# untitled.net
KiCad netlist of a schematic drawn in EAGLE
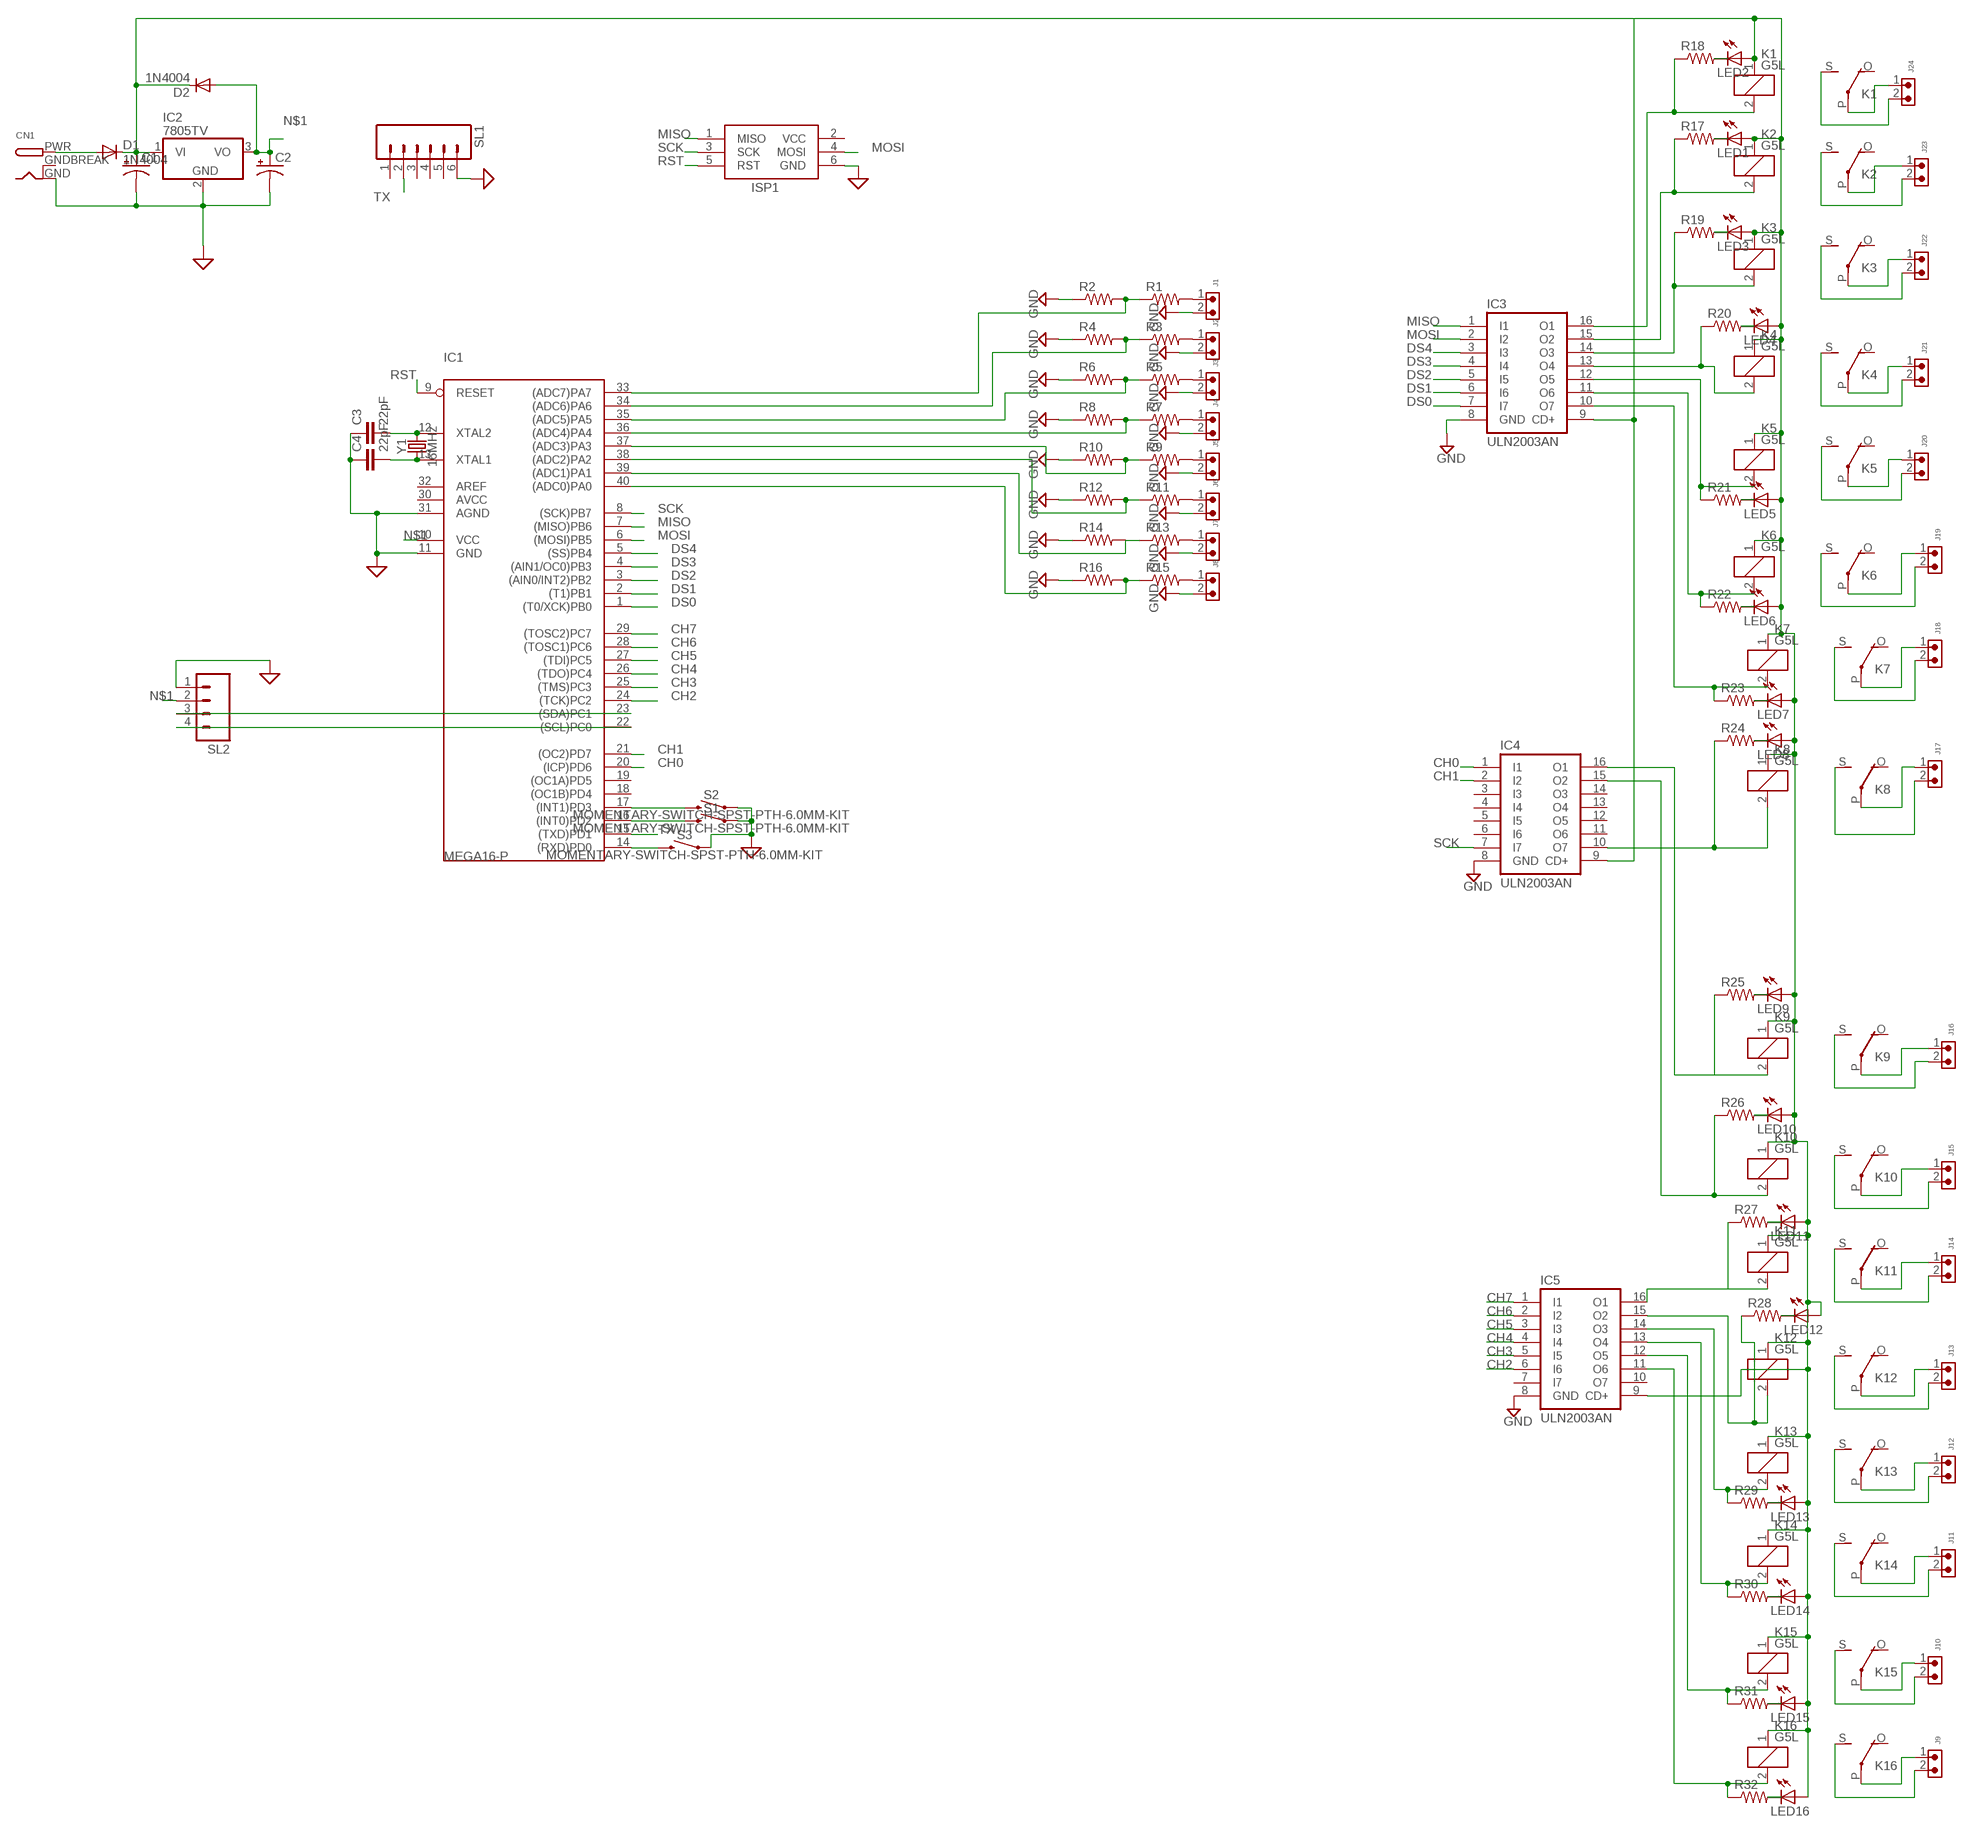
[diagram p0: schematic, sheet 1]

(export (version "E")
  (design (tool "Eeschema 10.0.6"))
  (components
    (comp (ref "C1")
      (value "CAPACITOR-PE5-10.5")
      (footprint "eagle-import:E5-10,5")
      (libsource (lib "eagle-import") (part "CAPACITOR-PE5-10.5"))
    )
    (comp (ref "C2")
      (value "CAPACITOR-PE5-6")
      (footprint "eagle-import:E5-6")
      (libsource (lib "eagle-import") (part "CAPACITOR-PE5-6"))
    )
    (comp (ref "C3")
      (value "22pF")
      (footprint "eagle-import:CAP-PTH-2.54")
      (libsource (lib "eagle-import") (part "22PF-PTH-2.54MM-200V-5%"))
    )
    (comp (ref "C4")
      (value "22pF")
      (footprint "eagle-import:CAP-PTH-2.54")
      (libsource (lib "eagle-import") (part "22PF-PTH-2.54MM-200V-5%"))
    )
    (comp (ref "CN1")
      (value "DCBARRELPTH")
      (footprint "eagle-import:DCJACK_2MM_PTH")
      (libsource (lib "eagle-import") (part "DCBARRELPTH"))
    )
    (comp (ref "D1")
      (value "1N4004")
      (footprint "eagle-import:DO41-10")
      (libsource (lib "eagle-import") (part "1N4004"))
    )
    (comp (ref "D2")
      (value "1N4004")
      (footprint "eagle-import:DO41-10")
      (libsource (lib "eagle-import") (part "1N4004"))
    )
    (comp (ref "IC1")
      (value "MEGA16-P")
      (footprint "eagle-import:DIL40")
      (libsource (lib "eagle-import") (part "MEGA16-P"))
    )
    (comp (ref "IC2")
      (value "7805TV")
      (footprint "eagle-import:TO220V")
      (libsource (lib "eagle-import") (part "78TV05"))
    )
    (comp (ref "IC3")
      (value "ULN2003AN")
      (footprint "eagle-import:DIL16")
      (libsource (lib "eagle-import") (part "ULN2003AN"))
    )
    (comp (ref "IC4")
      (value "ULN2003AN")
      (footprint "eagle-import:DIL16")
      (libsource (lib "eagle-import") (part "ULN2003AN"))
    )
    (comp (ref "IC5")
      (value "ULN2003AN")
      (footprint "eagle-import:DIL16")
      (libsource (lib "eagle-import") (part "ULN2003AN"))
    )
    (comp (ref "ISP1")
      (value "AVRISP-6")
      (footprint "eagle-import:AVRISP")
      (libsource (lib "eagle-import") (part "AVRISP-6"))
    )
    (comp (ref "J1")
      (value "691305530002")
      (footprint "eagle-import:691305530002")
      (libsource (lib "eagle-import") (part "691305530002"))
    )
    (comp (ref "J2")
      (value "691305530002")
      (footprint "eagle-import:691305530002")
      (libsource (lib "eagle-import") (part "691305530002"))
    )
    (comp (ref "J3")
      (value "691305530002")
      (footprint "eagle-import:691305530002")
      (libsource (lib "eagle-import") (part "691305530002"))
    )
    (comp (ref "J4")
      (value "691305530002")
      (footprint "eagle-import:691305530002")
      (libsource (lib "eagle-import") (part "691305530002"))
    )
    (comp (ref "J5")
      (value "691305530002")
      (footprint "eagle-import:691305530002")
      (libsource (lib "eagle-import") (part "691305530002"))
    )
    (comp (ref "J6")
      (value "691305530002")
      (footprint "eagle-import:691305530002")
      (libsource (lib "eagle-import") (part "691305530002"))
    )
    (comp (ref "J7")
      (value "691305530002")
      (footprint "eagle-import:691305530002")
      (libsource (lib "eagle-import") (part "691305530002"))
    )
    (comp (ref "J8")
      (value "691305530002")
      (footprint "eagle-import:691305530002")
      (libsource (lib "eagle-import") (part "691305530002"))
    )
    (comp (ref "J9")
      (value "691305530002")
      (footprint "eagle-import:691305530002")
      (libsource (lib "eagle-import") (part "691305530002"))
    )
    (comp (ref "J10")
      (value "691305530002")
      (footprint "eagle-import:691305530002")
      (libsource (lib "eagle-import") (part "691305530002"))
    )
    (comp (ref "J11")
      (value "691305530002")
      (footprint "eagle-import:691305530002")
      (libsource (lib "eagle-import") (part "691305530002"))
    )
    (comp (ref "J12")
      (value "691305530002")
      (footprint "eagle-import:691305530002")
      (libsource (lib "eagle-import") (part "691305530002"))
    )
    (comp (ref "J13")
      (value "691305530002")
      (footprint "eagle-import:691305530002")
      (libsource (lib "eagle-import") (part "691305530002"))
    )
    (comp (ref "J14")
      (value "691305530002")
      (footprint "eagle-import:691305530002")
      (libsource (lib "eagle-import") (part "691305530002"))
    )
    (comp (ref "J15")
      (value "691305530002")
      (footprint "eagle-import:691305530002")
      (libsource (lib "eagle-import") (part "691305530002"))
    )
    (comp (ref "J16")
      (value "691305530002")
      (footprint "eagle-import:691305530002")
      (libsource (lib "eagle-import") (part "691305530002"))
    )
    (comp (ref "J17")
      (value "691305530002")
      (footprint "eagle-import:691305530002")
      (libsource (lib "eagle-import") (part "691305530002"))
    )
    (comp (ref "J18")
      (value "691305530002")
      (footprint "eagle-import:691305530002")
      (libsource (lib "eagle-import") (part "691305530002"))
    )
    (comp (ref "J19")
      (value "691305530002")
      (footprint "eagle-import:691305530002")
      (libsource (lib "eagle-import") (part "691305530002"))
    )
    (comp (ref "J20")
      (value "691305530002")
      (footprint "eagle-import:691305530002")
      (libsource (lib "eagle-import") (part "691305530002"))
    )
    (comp (ref "J21")
      (value "691305530002")
      (footprint "eagle-import:691305530002")
      (libsource (lib "eagle-import") (part "691305530002"))
    )
    (comp (ref "J22")
      (value "691305530002")
      (footprint "eagle-import:691305530002")
      (libsource (lib "eagle-import") (part "691305530002"))
    )
    (comp (ref "J23")
      (value "691305530002")
      (footprint "eagle-import:691305530002")
      (libsource (lib "eagle-import") (part "691305530002"))
    )
    (comp (ref "J24")
      (value "691305530002")
      (footprint "eagle-import:691305530002")
      (libsource (lib "eagle-import") (part "691305530002"))
    )
    (comp (ref "K1")
      (value "G5L")
      (footprint "eagle-import:G5LE")
      (libsource (lib "eagle-import") (part "G5L"))
    )
    (comp (ref "K2")
      (value "G5L")
      (footprint "eagle-import:G5LE")
      (libsource (lib "eagle-import") (part "G5L"))
    )
    (comp (ref "K3")
      (value "G5L")
      (footprint "eagle-import:G5LE")
      (libsource (lib "eagle-import") (part "G5L"))
    )
    (comp (ref "K4")
      (value "G5L")
      (footprint "eagle-import:G5LE")
      (libsource (lib "eagle-import") (part "G5L"))
    )
    (comp (ref "K5")
      (value "G5L")
      (footprint "eagle-import:G5LE")
      (libsource (lib "eagle-import") (part "G5L"))
    )
    (comp (ref "K6")
      (value "G5L")
      (footprint "eagle-import:G5LE")
      (libsource (lib "eagle-import") (part "G5L"))
    )
    (comp (ref "K7")
      (value "G5L")
      (footprint "eagle-import:G5LE")
      (libsource (lib "eagle-import") (part "G5L"))
    )
    (comp (ref "K8")
      (value "G5L")
      (footprint "eagle-import:G5LE")
      (libsource (lib "eagle-import") (part "G5L"))
    )
    (comp (ref "K9")
      (value "G5L")
      (footprint "eagle-import:G5LE")
      (libsource (lib "eagle-import") (part "G5L"))
    )
    (comp (ref "K10")
      (value "G5L")
      (footprint "eagle-import:G5LE")
      (libsource (lib "eagle-import") (part "G5L"))
    )
    (comp (ref "K11")
      (value "G5L")
      (footprint "eagle-import:G5LE")
      (libsource (lib "eagle-import") (part "G5L"))
    )
    (comp (ref "K12")
      (value "G5L")
      (footprint "eagle-import:G5LE")
      (libsource (lib "eagle-import") (part "G5L"))
    )
    (comp (ref "K13")
      (value "G5L")
      (footprint "eagle-import:G5LE")
      (libsource (lib "eagle-import") (part "G5L"))
    )
    (comp (ref "K14")
      (value "G5L")
      (footprint "eagle-import:G5LE")
      (libsource (lib "eagle-import") (part "G5L"))
    )
    (comp (ref "K15")
      (value "G5L")
      (footprint "eagle-import:G5LE")
      (libsource (lib "eagle-import") (part "G5L"))
    )
    (comp (ref "K16")
      (value "G5L")
      (footprint "eagle-import:G5LE")
      (libsource (lib "eagle-import") (part "G5L"))
    )
    (comp (ref "LED1")
      (value "LED5MM")
      (footprint "eagle-import:LED5MM")
      (libsource (lib "eagle-import") (part "LED5MM"))
    )
    (comp (ref "LED2")
      (value "LED5MM")
      (footprint "eagle-import:LED5MM")
      (libsource (lib "eagle-import") (part "LED5MM"))
    )
    (comp (ref "LED3")
      (value "LED5MM")
      (footprint "eagle-import:LED5MM")
      (libsource (lib "eagle-import") (part "LED5MM"))
    )
    (comp (ref "LED4")
      (value "LED5MM")
      (footprint "eagle-import:LED5MM")
      (libsource (lib "eagle-import") (part "LED5MM"))
    )
    (comp (ref "LED5")
      (value "LED5MM")
      (footprint "eagle-import:LED5MM")
      (libsource (lib "eagle-import") (part "LED5MM"))
    )
    (comp (ref "LED6")
      (value "LED5MM")
      (footprint "eagle-import:LED5MM")
      (libsource (lib "eagle-import") (part "LED5MM"))
    )
    (comp (ref "LED7")
      (value "LED5MM")
      (footprint "eagle-import:LED5MM")
      (libsource (lib "eagle-import") (part "LED5MM"))
    )
    (comp (ref "LED8")
      (value "LED5MM")
      (footprint "eagle-import:LED5MM")
      (libsource (lib "eagle-import") (part "LED5MM"))
    )
    (comp (ref "LED9")
      (value "LED5MM")
      (footprint "eagle-import:LED5MM")
      (libsource (lib "eagle-import") (part "LED5MM"))
    )
    (comp (ref "LED10")
      (value "LED5MM")
      (footprint "eagle-import:LED5MM")
      (libsource (lib "eagle-import") (part "LED5MM"))
    )
    (comp (ref "LED11")
      (value "LED5MM")
      (footprint "eagle-import:LED5MM")
      (libsource (lib "eagle-import") (part "LED5MM"))
    )
    (comp (ref "LED12")
      (value "LED5MM")
      (footprint "eagle-import:LED5MM")
      (libsource (lib "eagle-import") (part "LED5MM"))
    )
    (comp (ref "LED13")
      (value "LED5MM")
      (footprint "eagle-import:LED5MM")
      (libsource (lib "eagle-import") (part "LED5MM"))
    )
    (comp (ref "LED14")
      (value "LED5MM")
      (footprint "eagle-import:LED5MM")
      (libsource (lib "eagle-import") (part "LED5MM"))
    )
    (comp (ref "LED15")
      (value "LED5MM")
      (footprint "eagle-import:LED5MM")
      (libsource (lib "eagle-import") (part "LED5MM"))
    )
    (comp (ref "LED16")
      (value "LED5MM")
      (footprint "eagle-import:LED5MM")
      (libsource (lib "eagle-import") (part "LED5MM"))
    )
    (comp (ref "R1")
      (value "R-US_0309/12")
      (footprint "eagle-import:0309_12")
      (libsource (lib "eagle-import") (part "R-US_0309/12"))
    )
    (comp (ref "R2")
      (value "R-US_0309/12")
      (footprint "eagle-import:0309_12")
      (libsource (lib "eagle-import") (part "R-US_0309/12"))
    )
    (comp (ref "R3")
      (value "R-US_0309/12")
      (footprint "eagle-import:0309_12")
      (libsource (lib "eagle-import") (part "R-US_0309/12"))
    )
    (comp (ref "R4")
      (value "R-US_0309/12")
      (footprint "eagle-import:0309_12")
      (libsource (lib "eagle-import") (part "R-US_0309/12"))
    )
    (comp (ref "R5")
      (value "R-US_0309/12")
      (footprint "eagle-import:0309_12")
      (libsource (lib "eagle-import") (part "R-US_0309/12"))
    )
    (comp (ref "R6")
      (value "R-US_0309/12")
      (footprint "eagle-import:0309_12")
      (libsource (lib "eagle-import") (part "R-US_0309/12"))
    )
    (comp (ref "R7")
      (value "R-US_0309/12")
      (footprint "eagle-import:0309_12")
      (libsource (lib "eagle-import") (part "R-US_0309/12"))
    )
    (comp (ref "R8")
      (value "R-US_0309/12")
      (footprint "eagle-import:0309_12")
      (libsource (lib "eagle-import") (part "R-US_0309/12"))
    )
    (comp (ref "R9")
      (value "R-US_0309/12")
      (footprint "eagle-import:0309_12")
      (libsource (lib "eagle-import") (part "R-US_0309/12"))
    )
    (comp (ref "R10")
      (value "R-US_0309/12")
      (footprint "eagle-import:0309_12")
      (libsource (lib "eagle-import") (part "R-US_0309/12"))
    )
    (comp (ref "R11")
      (value "R-US_0309/12")
      (footprint "eagle-import:0309_12")
      (libsource (lib "eagle-import") (part "R-US_0309/12"))
    )
    (comp (ref "R12")
      (value "R-US_0309/12")
      (footprint "eagle-import:0309_12")
      (libsource (lib "eagle-import") (part "R-US_0309/12"))
    )
    (comp (ref "R13")
      (value "R-US_0309/12")
      (footprint "eagle-import:0309_12")
      (libsource (lib "eagle-import") (part "R-US_0309/12"))
    )
    (comp (ref "R14")
      (value "R-US_0309/12")
      (footprint "eagle-import:0309_12")
      (libsource (lib "eagle-import") (part "R-US_0309/12"))
    )
    (comp (ref "R15")
      (value "R-US_0309/12")
      (footprint "eagle-import:0309_12")
      (libsource (lib "eagle-import") (part "R-US_0309/12"))
    )
    (comp (ref "R16")
      (value "R-US_0309/12")
      (footprint "eagle-import:0309_12")
      (libsource (lib "eagle-import") (part "R-US_0309/12"))
    )
    (comp (ref "R17")
      (value "R-US_0204/5")
      (footprint "eagle-import:0204_5")
      (libsource (lib "eagle-import") (part "adafruit_420_R-US_0204/5"))
    )
    (comp (ref "R18")
      (value "R-US_0204/5")
      (footprint "eagle-import:0204_5")
      (libsource (lib "eagle-import") (part "adafruit_420_R-US_0204/5"))
    )
    (comp (ref "R19")
      (value "R-US_0204/5")
      (footprint "eagle-import:0204_5")
      (libsource (lib "eagle-import") (part "adafruit_420_R-US_0204/5"))
    )
    (comp (ref "R20")
      (value "R-US_0204/5")
      (footprint "eagle-import:0204_5")
      (libsource (lib "eagle-import") (part "adafruit_420_R-US_0204/5"))
    )
    (comp (ref "R21")
      (value "R-US_0204/5")
      (footprint "eagle-import:0204_5")
      (libsource (lib "eagle-import") (part "adafruit_420_R-US_0204/5"))
    )
    (comp (ref "R22")
      (value "R-US_0207/10")
      (footprint "eagle-import:0207_10")
      (libsource (lib "eagle-import") (part "adafruit_420_R-US_0207/10"))
    )
    (comp (ref "R23")
      (value "R-US_0207/10")
      (footprint "eagle-import:0207_10")
      (libsource (lib "eagle-import") (part "adafruit_420_R-US_0207/10"))
    )
    (comp (ref "R24")
      (value "R-US_0204/5")
      (footprint "eagle-import:0204_5")
      (libsource (lib "eagle-import") (part "adafruit_420_R-US_0204/5"))
    )
    (comp (ref "R25")
      (value "R-US_0207/10")
      (footprint "eagle-import:0207_10")
      (libsource (lib "eagle-import") (part "adafruit_420_R-US_0207/10"))
    )
    (comp (ref "R26")
      (value "R-US_0207/10")
      (footprint "eagle-import:0207_10")
      (libsource (lib "eagle-import") (part "adafruit_420_R-US_0207/10"))
    )
    (comp (ref "R27")
      (value "R-US_0207/10")
      (footprint "eagle-import:0207_10")
      (libsource (lib "eagle-import") (part "adafruit_420_R-US_0207/10"))
    )
    (comp (ref "R28")
      (value "R-US_0207/10")
      (footprint "eagle-import:0207_10")
      (libsource (lib "eagle-import") (part "adafruit_420_R-US_0207/10"))
    )
    (comp (ref "R29")
      (value "R-US_0207/10")
      (footprint "eagle-import:0207_10")
      (libsource (lib "eagle-import") (part "adafruit_420_R-US_0207/10"))
    )
    (comp (ref "R30")
      (value "R-US_0207/10")
      (footprint "eagle-import:0207_10")
      (libsource (lib "eagle-import") (part "adafruit_420_R-US_0207/10"))
    )
    (comp (ref "R31")
      (value "R-US_0207/10")
      (footprint "eagle-import:0207_10")
      (libsource (lib "eagle-import") (part "adafruit_420_R-US_0207/10"))
    )
    (comp (ref "R32")
      (value "R-US_0207/10")
      (footprint "eagle-import:0207_10")
      (libsource (lib "eagle-import") (part "adafruit_420_R-US_0207/10"))
    )
    (comp (ref "S1")
      (value "MOMENTARY-SWITCH-SPST-PTH-6.0MM-KIT")
      (footprint "eagle-import:TACTILE_SWITCH_PTH_6.0MM_KIT")
      (libsource (lib "eagle-import") (part "MOMENTARY-SWITCH-SPST-PTH-6.0MM-KIT"))
    )
    (comp (ref "S2")
      (value "MOMENTARY-SWITCH-SPST-PTH-6.0MM-KIT")
      (footprint "eagle-import:TACTILE_SWITCH_PTH_6.0MM_KIT")
      (libsource (lib "eagle-import") (part "MOMENTARY-SWITCH-SPST-PTH-6.0MM-KIT"))
    )
    (comp (ref "S3")
      (value "MOMENTARY-SWITCH-SPST-PTH-6.0MM-KIT")
      (footprint "eagle-import:TACTILE_SWITCH_PTH_6.0MM_KIT")
      (libsource (lib "eagle-import") (part "MOMENTARY-SWITCH-SPST-PTH-6.0MM-KIT"))
    )
    (comp (ref "SL1")
      (value "M06")
      (footprint "eagle-import:06P")
      (libsource (lib "eagle-import") (part "M06"))
    )
    (comp (ref "SL2")
      (value "M04")
      (footprint "eagle-import:04P")
      (libsource (lib "eagle-import") (part "M04"))
    )
    (comp (ref "Y1")
      (value "16MHz")
      (footprint "eagle-import:HC49US")
      (libsource (lib "eagle-import") (part "CRYSTAL-16MHZPTH-HC49US"))
    )
  )
  (nets
    (net (code "1") (name "/AREF") (class "Default")
      (node (ref "IC1") (pin "32") (pinfunction "AREF_32") (pintype "power_in"))
    )
    (net (code "2") (name "/AVCC") (class "Default")
      (node (ref "IC1") (pin "30") (pinfunction "AVCC_30") (pintype "power_in"))
    )
    (net (code "3") (name "/CH0") (class "Default")
      (node (ref "IC1") (pin "20") (pinfunction "(ICP)PD6_20") (pintype "bidirectional"))
      (node (ref "IC4") (pin "1") (pinfunction "I1_1") (pintype "input"))
    )
    (net (code "4") (name "/CH1") (class "Default")
      (node (ref "IC1") (pin "21") (pinfunction "(OC2)PD7_21") (pintype "bidirectional"))
      (node (ref "IC4") (pin "2") (pinfunction "I2_2") (pintype "input"))
    )
    (net (code "5") (name "/CH2") (class "Default")
      (node (ref "IC1") (pin "24") (pinfunction "(TCK)PC2_24") (pintype "bidirectional"))
      (node (ref "IC5") (pin "6") (pinfunction "I6_6") (pintype "input"))
    )
    (net (code "6") (name "/CH3") (class "Default")
      (node (ref "IC1") (pin "25") (pinfunction "(TMS)PC3_25") (pintype "bidirectional"))
      (node (ref "IC5") (pin "5") (pinfunction "I5_5") (pintype "input"))
    )
    (net (code "7") (name "/CH4") (class "Default")
      (node (ref "IC1") (pin "26") (pinfunction "(TDO)PC4_26") (pintype "bidirectional"))
      (node (ref "IC5") (pin "4") (pinfunction "I4_4") (pintype "input"))
    )
    (net (code "8") (name "/CH5") (class "Default")
      (node (ref "IC1") (pin "27") (pinfunction "(TDI)PC5_27") (pintype "bidirectional"))
      (node (ref "IC5") (pin "3") (pinfunction "I3_3") (pintype "input"))
    )
    (net (code "9") (name "/CH6") (class "Default")
      (node (ref "IC1") (pin "28") (pinfunction "(TOSC1)PC6_28") (pintype "bidirectional"))
      (node (ref "IC5") (pin "2") (pinfunction "I2_2") (pintype "input"))
    )
    (net (code "10") (name "/CH7") (class "Default")
      (node (ref "IC1") (pin "29") (pinfunction "(TOSC2)PC7_29") (pintype "bidirectional"))
      (node (ref "IC5") (pin "1") (pinfunction "I1_1") (pintype "input"))
    )
    (net (code "11") (name "/DS0") (class "Default")
      (node (ref "IC1") (pin "1") (pinfunction "(T0/XCK)PB0_1") (pintype "bidirectional"))
      (node (ref "IC3") (pin "7") (pinfunction "I7_7") (pintype "input"))
    )
    (net (code "12") (name "/DS1") (class "Default")
      (node (ref "IC1") (pin "2") (pinfunction "(T1)PB1_2") (pintype "bidirectional"))
      (node (ref "IC3") (pin "6") (pinfunction "I6_6") (pintype "input"))
    )
    (net (code "13") (name "/DS2") (class "Default")
      (node (ref "IC1") (pin "3") (pinfunction "(AIN0/INT2)PB2_3") (pintype "bidirectional"))
      (node (ref "IC3") (pin "5") (pinfunction "I5_5") (pintype "input"))
    )
    (net (code "14") (name "/DS3") (class "Default")
      (node (ref "IC1") (pin "4") (pinfunction "(AIN1/OC0)PB3_4") (pintype "bidirectional"))
      (node (ref "IC3") (pin "4") (pinfunction "I4_4") (pintype "input"))
    )
    (net (code "15") (name "/DS4") (class "Default")
      (node (ref "IC1") (pin "5") (pinfunction "(SS)PB4_5") (pintype "bidirectional"))
      (node (ref "IC3") (pin "3") (pinfunction "I3_3") (pintype "input"))
    )
    (net (code "16") (name "/GNDBREAK") (class "Default")
      (node (ref "CN1") (pin "GNDBREAK") (pinfunction "GNDBREAK_GNDBREAK") (pintype "power_in"))
    )
    (net (code "17") (name "/MISO") (class "Default")
      (node (ref "IC1") (pin "7") (pinfunction "(MISO)PB6_7") (pintype "bidirectional"))
      (node (ref "IC3") (pin "1") (pinfunction "I1_1") (pintype "input"))
      (node (ref "ISP1") (pin "1") (pinfunction "MISO_1") (pintype "input"))
    )
    (net (code "18") (name "/MOSI") (class "Default")
      (node (ref "IC1") (pin "6") (pinfunction "(MOSI)PB5_6") (pintype "bidirectional"))
      (node (ref "IC3") (pin "2") (pinfunction "I2_2") (pintype "input"))
      (node (ref "ISP1") (pin "4") (pinfunction "MOSI_4") (pintype "output"))
    )
    (net (code "19") (name "/N$1") (class "Default")
      (node (ref "C2") (pin "+") (pinfunction "+_+") (pintype "passive"))
      (node (ref "D2") (pin "A") (pinfunction "A_A") (pintype "passive"))
      (node (ref "IC1") (pin "10") (pinfunction "VCC_10") (pintype "power_in"))
      (node (ref "IC2") (pin "3") (pinfunction "VO_3") (pintype "passive"))
      (node (ref "SL2") (pin "2") (pinfunction "2_2") (pintype "passive"))
    )
    (net (code "20") (name "/RST") (class "Default")
      (node (ref "IC1") (pin "9") (pinfunction "RESET_9") (pintype "input"))
      (node (ref "ISP1") (pin "5") (pinfunction "RST_5") (pintype "output"))
    )
    (net (code "21") (name "/SCK") (class "Default")
      (node (ref "IC1") (pin "8") (pinfunction "(SCK)PB7_8") (pintype "bidirectional"))
      (node (ref "IC4") (pin "7") (pinfunction "I7_7") (pintype "input"))
      (node (ref "ISP1") (pin "3") (pinfunction "SCK_3") (pintype "output"))
    )
    (net (code "22") (name "/TX") (class "Default")
      (node (ref "IC1") (pin "15") (pinfunction "(TXD)PD1_15") (pintype "bidirectional"))
      (node (ref "SL1") (pin "2") (pinfunction "2_2") (pintype "passive"))
    )
    (net (code "23") (name "/VCC") (class "Default")
      (node (ref "ISP1") (pin "2") (pinfunction "VCC_2") (pintype "power_in"))
    )
    (net (code "24") (name "GND") (class "Default")
      (node (ref "C1") (pin "-") (pinfunction "-_-") (pintype "passive"))
      (node (ref "C2") (pin "-") (pinfunction "-_-") (pintype "passive"))
      (node (ref "C3") (pin "1") (pinfunction "1_1") (pintype "passive"))
      (node (ref "C4") (pin "1") (pinfunction "1_1") (pintype "passive"))
      (node (ref "CN1") (pin "GND") (pinfunction "GND_GND") (pintype "power_in"))
      (node (ref "IC1") (pin "11") (pinfunction "GND_11") (pintype "power_in"))
      (node (ref "IC1") (pin "31") (pinfunction "AGND_31") (pintype "power_in"))
      (node (ref "IC2") (pin "2") (pinfunction "GND_2") (pintype "passive"))
      (node (ref "IC3") (pin "8") (pinfunction "GND_8") (pintype "power_in"))
      (node (ref "IC4") (pin "8") (pinfunction "GND_8") (pintype "power_in"))
      (node (ref "IC5") (pin "8") (pinfunction "GND_8") (pintype "power_in"))
      (node (ref "ISP1") (pin "6") (pinfunction "GND_6") (pintype "power_in"))
      (node (ref "J1") (pin "2") (pinfunction "2_2") (pintype "passive"))
      (node (ref "J2") (pin "2") (pinfunction "2_2") (pintype "passive"))
      (node (ref "J3") (pin "2") (pinfunction "2_2") (pintype "passive"))
      (node (ref "J4") (pin "2") (pinfunction "2_2") (pintype "passive"))
      (node (ref "J5") (pin "2") (pinfunction "2_2") (pintype "passive"))
      (node (ref "J6") (pin "2") (pinfunction "2_2") (pintype "passive"))
      (node (ref "J7") (pin "2") (pinfunction "2_2") (pintype "passive"))
      (node (ref "J8") (pin "2") (pinfunction "2_2") (pintype "passive"))
      (node (ref "R10") (pin "1") (pinfunction "1_1") (pintype "passive"))
      (node (ref "R12") (pin "1") (pinfunction "1_1") (pintype "passive"))
      (node (ref "R14") (pin "1") (pinfunction "1_1") (pintype "passive"))
      (node (ref "R16") (pin "1") (pinfunction "1_1") (pintype "passive"))
      (node (ref "R2") (pin "1") (pinfunction "1_1") (pintype "passive"))
      (node (ref "R4") (pin "1") (pinfunction "1_1") (pintype "passive"))
      (node (ref "R6") (pin "1") (pinfunction "1_1") (pintype "passive"))
      (node (ref "R8") (pin "1") (pinfunction "1_1") (pintype "passive"))
      (node (ref "S1") (pin "1") (pinfunction "1_1") (pintype "passive"))
      (node (ref "S2") (pin "1") (pinfunction "1_1") (pintype "passive"))
      (node (ref "S3") (pin "1") (pinfunction "1_1") (pintype "passive"))
      (node (ref "SL1") (pin "6") (pinfunction "6_6") (pintype "passive"))
      (node (ref "SL2") (pin "1") (pinfunction "1_1") (pintype "passive"))
    )
    (net (code "25") (name "Net-(CN1-PadPWR)") (class "Default")
      (node (ref "CN1") (pin "PWR") (pinfunction "PWR_PWR") (pintype "power_in"))
      (node (ref "D1") (pin "A") (pinfunction "A_A") (pintype "passive"))
    )
    (net (code "26") (name "Net-(IC1-(ADC0)PA0)") (class "Default")
      (node (ref "IC1") (pin "40") (pinfunction "(ADC0)PA0_40") (pintype "bidirectional"))
      (node (ref "R15") (pin "1") (pinfunction "1_1") (pintype "passive"))
      (node (ref "R16") (pin "2") (pinfunction "2_2") (pintype "passive"))
    )
    (net (code "27") (name "Net-(IC1-(ADC1)PA1)") (class "Default")
      (node (ref "IC1") (pin "39") (pinfunction "(ADC1)PA1_39") (pintype "bidirectional"))
      (node (ref "R13") (pin "1") (pinfunction "1_1") (pintype "passive"))
      (node (ref "R14") (pin "2") (pinfunction "2_2") (pintype "passive"))
    )
    (net (code "28") (name "Net-(IC1-(ADC2)PA2)") (class "Default")
      (node (ref "IC1") (pin "38") (pinfunction "(ADC2)PA2_38") (pintype "bidirectional"))
      (node (ref "R11") (pin "1") (pinfunction "1_1") (pintype "passive"))
      (node (ref "R12") (pin "2") (pinfunction "2_2") (pintype "passive"))
    )
    (net (code "29") (name "Net-(IC1-(ADC3)PA3)") (class "Default")
      (node (ref "IC1") (pin "37") (pinfunction "(ADC3)PA3_37") (pintype "bidirectional"))
      (node (ref "R10") (pin "2") (pinfunction "2_2") (pintype "passive"))
      (node (ref "R9") (pin "1") (pinfunction "1_1") (pintype "passive"))
    )
    (net (code "30") (name "Net-(IC1-(ADC4)PA4)") (class "Default")
      (node (ref "IC1") (pin "36") (pinfunction "(ADC4)PA4_36") (pintype "bidirectional"))
      (node (ref "R7") (pin "1") (pinfunction "1_1") (pintype "passive"))
      (node (ref "R8") (pin "2") (pinfunction "2_2") (pintype "passive"))
    )
    (net (code "31") (name "Net-(IC1-(ADC5)PA5)") (class "Default")
      (node (ref "IC1") (pin "35") (pinfunction "(ADC5)PA5_35") (pintype "bidirectional"))
      (node (ref "R5") (pin "1") (pinfunction "1_1") (pintype "passive"))
      (node (ref "R6") (pin "2") (pinfunction "2_2") (pintype "passive"))
    )
    (net (code "32") (name "Net-(IC1-(ADC6)PA6)") (class "Default")
      (node (ref "IC1") (pin "34") (pinfunction "(ADC6)PA6_34") (pintype "bidirectional"))
      (node (ref "R3") (pin "1") (pinfunction "1_1") (pintype "passive"))
      (node (ref "R4") (pin "2") (pinfunction "2_2") (pintype "passive"))
    )
    (net (code "33") (name "Net-(IC1-(ADC7)PA7)") (class "Default")
      (node (ref "IC1") (pin "33") (pinfunction "(ADC7)PA7_33") (pintype "bidirectional"))
      (node (ref "R1") (pin "1") (pinfunction "1_1") (pintype "passive"))
      (node (ref "R2") (pin "2") (pinfunction "2_2") (pintype "passive"))
    )
    (net (code "34") (name "Net-(IC1-(INT0)PD2)") (class "Default")
      (node (ref "IC1") (pin "16") (pinfunction "(INT0)PD2_16") (pintype "bidirectional"))
      (node (ref "S1") (pin "3") (pinfunction "2_3") (pintype "passive"))
    )
    (net (code "35") (name "Net-(IC1-(INT1)PD3)") (class "Default")
      (node (ref "IC1") (pin "17") (pinfunction "(INT1)PD3_17") (pintype "bidirectional"))
      (node (ref "S2") (pin "3") (pinfunction "2_3") (pintype "passive"))
    )
    (net (code "36") (name "Net-(IC1-(RXD)PD0)") (class "Default")
      (node (ref "IC1") (pin "14") (pinfunction "(RXD)PD0_14") (pintype "bidirectional"))
      (node (ref "S3") (pin "3") (pinfunction "2_3") (pintype "passive"))
    )
    (net (code "37") (name "Net-(IC1-(SCL)PC0)") (class "Default")
      (node (ref "IC1") (pin "22") (pinfunction "(SCL)PC0_22") (pintype "bidirectional"))
      (node (ref "SL2") (pin "4") (pinfunction "4_4") (pintype "passive"))
    )
    (net (code "38") (name "Net-(IC1-(SDA)PC1)") (class "Default")
      (node (ref "IC1") (pin "23") (pinfunction "(SDA)PC1_23") (pintype "bidirectional"))
      (node (ref "SL2") (pin "3") (pinfunction "3_3") (pintype "passive"))
    )
    (net (code "39") (name "Net-(IC1-XTAL1)") (class "Default")
      (node (ref "C4") (pin "2") (pinfunction "2_2") (pintype "passive"))
      (node (ref "IC1") (pin "13") (pinfunction "XTAL1_13") (pintype "bidirectional"))
      (node (ref "Y1") (pin "1") (pinfunction "1_1") (pintype "passive"))
    )
    (net (code "40") (name "Net-(IC1-XTAL2)") (class "Default")
      (node (ref "C3") (pin "2") (pinfunction "2_2") (pintype "passive"))
      (node (ref "IC1") (pin "12") (pinfunction "XTAL2_12") (pintype "bidirectional"))
      (node (ref "Y1") (pin "2") (pinfunction "2_2") (pintype "passive"))
    )
    (net (code "41") (name "Net-(IC2-VI)") (class "Default")
      (node (ref "C1") (pin "+") (pinfunction "+_+") (pintype "passive"))
      (node (ref "D1") (pin "C") (pinfunction "C_C") (pintype "passive"))
      (node (ref "D2") (pin "C") (pinfunction "C_C") (pintype "passive"))
      (node (ref "IC2") (pin "1") (pinfunction "VI_1") (pintype "input"))
      (node (ref "IC3") (pin "9") (pinfunction "CD+_9") (pintype "passive"))
      (node (ref "IC4") (pin "9") (pinfunction "CD+_9") (pintype "passive"))
      (node (ref "IC5") (pin "9") (pinfunction "CD+_9") (pintype "passive"))
      (node (ref "K1") (pin "1") (pinfunction "1_1") (pintype "passive"))
      (node (ref "K10") (pin "1") (pinfunction "1_1") (pintype "passive"))
      (node (ref "K11") (pin "1") (pinfunction "1_1") (pintype "passive"))
      (node (ref "K12") (pin "1") (pinfunction "1_1") (pintype "passive"))
      (node (ref "K13") (pin "1") (pinfunction "1_1") (pintype "passive"))
      (node (ref "K14") (pin "1") (pinfunction "1_1") (pintype "passive"))
      (node (ref "K15") (pin "1") (pinfunction "1_1") (pintype "passive"))
      (node (ref "K16") (pin "1") (pinfunction "1_1") (pintype "passive"))
      (node (ref "K2") (pin "1") (pinfunction "1_1") (pintype "passive"))
      (node (ref "K3") (pin "1") (pinfunction "1_1") (pintype "passive"))
      (node (ref "K4") (pin "1") (pinfunction "1_1") (pintype "passive"))
      (node (ref "K5") (pin "1") (pinfunction "1_1") (pintype "passive"))
      (node (ref "K6") (pin "1") (pinfunction "1_1") (pintype "passive"))
      (node (ref "K7") (pin "1") (pinfunction "1_1") (pintype "passive"))
      (node (ref "K8") (pin "1") (pinfunction "1_1") (pintype "passive"))
      (node (ref "K9") (pin "1") (pinfunction "1_1") (pintype "passive"))
      (node (ref "LED1") (pin "A") (pinfunction "A_A") (pintype "passive"))
      (node (ref "LED10") (pin "A") (pinfunction "A_A") (pintype "passive"))
      (node (ref "LED11") (pin "A") (pinfunction "A_A") (pintype "passive"))
      (node (ref "LED12") (pin "A") (pinfunction "A_A") (pintype "passive"))
      (node (ref "LED13") (pin "A") (pinfunction "A_A") (pintype "passive"))
      (node (ref "LED14") (pin "A") (pinfunction "A_A") (pintype "passive"))
      (node (ref "LED15") (pin "A") (pinfunction "A_A") (pintype "passive"))
      (node (ref "LED16") (pin "A") (pinfunction "A_A") (pintype "passive"))
      (node (ref "LED2") (pin "A") (pinfunction "A_A") (pintype "passive"))
      (node (ref "LED3") (pin "A") (pinfunction "A_A") (pintype "passive"))
      (node (ref "LED4") (pin "A") (pinfunction "A_A") (pintype "passive"))
      (node (ref "LED5") (pin "A") (pinfunction "A_A") (pintype "passive"))
      (node (ref "LED6") (pin "A") (pinfunction "A_A") (pintype "passive"))
      (node (ref "LED7") (pin "A") (pinfunction "A_A") (pintype "passive"))
      (node (ref "LED8") (pin "A") (pinfunction "A_A") (pintype "passive"))
      (node (ref "LED9") (pin "A") (pinfunction "A_A") (pintype "passive"))
    )
    (net (code "42") (name "Net-(IC3-O1)") (class "Default")
      (node (ref "IC3") (pin "16") (pinfunction "O1_16") (pintype "open_collector"))
      (node (ref "K1") (pin "2") (pinfunction "2_2") (pintype "passive"))
      (node (ref "R18") (pin "1") (pinfunction "1_1") (pintype "passive"))
    )
    (net (code "43") (name "Net-(IC3-O2)") (class "Default")
      (node (ref "IC3") (pin "15") (pinfunction "O2_15") (pintype "open_collector"))
      (node (ref "K2") (pin "2") (pinfunction "2_2") (pintype "passive"))
      (node (ref "R17") (pin "1") (pinfunction "1_1") (pintype "passive"))
    )
    (net (code "44") (name "Net-(IC3-O3)") (class "Default")
      (node (ref "IC3") (pin "14") (pinfunction "O3_14") (pintype "open_collector"))
      (node (ref "K3") (pin "2") (pinfunction "2_2") (pintype "passive"))
      (node (ref "R19") (pin "1") (pinfunction "1_1") (pintype "passive"))
    )
    (net (code "45") (name "Net-(IC3-O4)") (class "Default")
      (node (ref "IC3") (pin "13") (pinfunction "O4_13") (pintype "open_collector"))
      (node (ref "K4") (pin "2") (pinfunction "2_2") (pintype "passive"))
      (node (ref "R20") (pin "1") (pinfunction "1_1") (pintype "passive"))
    )
    (net (code "46") (name "Net-(IC3-O5)") (class "Default")
      (node (ref "IC3") (pin "12") (pinfunction "O5_12") (pintype "open_collector"))
      (node (ref "K5") (pin "2") (pinfunction "2_2") (pintype "passive"))
      (node (ref "R21") (pin "1") (pinfunction "1_1") (pintype "passive"))
    )
    (net (code "47") (name "Net-(IC3-O6)") (class "Default")
      (node (ref "IC3") (pin "11") (pinfunction "O6_11") (pintype "open_collector"))
      (node (ref "K6") (pin "2") (pinfunction "2_2") (pintype "passive"))
      (node (ref "R22") (pin "1") (pinfunction "1_1") (pintype "passive"))
    )
    (net (code "48") (name "Net-(IC3-O7)") (class "Default")
      (node (ref "IC3") (pin "10") (pinfunction "O7_10") (pintype "open_collector"))
      (node (ref "K7") (pin "2") (pinfunction "2_2") (pintype "passive"))
      (node (ref "R23") (pin "1") (pinfunction "1_1") (pintype "passive"))
    )
    (net (code "49") (name "Net-(IC4-O1)") (class "Default")
      (node (ref "IC4") (pin "16") (pinfunction "O1_16") (pintype "open_collector"))
      (node (ref "K9") (pin "2") (pinfunction "2_2") (pintype "passive"))
      (node (ref "R25") (pin "1") (pinfunction "1_1") (pintype "passive"))
    )
    (net (code "50") (name "Net-(IC4-O2)") (class "Default")
      (node (ref "IC4") (pin "15") (pinfunction "O2_15") (pintype "open_collector"))
      (node (ref "K10") (pin "2") (pinfunction "2_2") (pintype "passive"))
      (node (ref "R26") (pin "1") (pinfunction "1_1") (pintype "passive"))
    )
    (net (code "51") (name "Net-(IC4-O7)") (class "Default")
      (node (ref "IC4") (pin "10") (pinfunction "O7_10") (pintype "open_collector"))
      (node (ref "K8") (pin "2") (pinfunction "2_2") (pintype "passive"))
      (node (ref "R24") (pin "1") (pinfunction "1_1") (pintype "passive"))
    )
    (net (code "52") (name "Net-(IC5-O1)") (class "Default")
      (node (ref "IC5") (pin "16") (pinfunction "O1_16") (pintype "open_collector"))
      (node (ref "K11") (pin "2") (pinfunction "2_2") (pintype "passive"))
      (node (ref "R27") (pin "1") (pinfunction "1_1") (pintype "passive"))
    )
    (net (code "53") (name "Net-(IC5-O2)") (class "Default")
      (node (ref "IC5") (pin "15") (pinfunction "O2_15") (pintype "open_collector"))
      (node (ref "K12") (pin "2") (pinfunction "2_2") (pintype "passive"))
      (node (ref "R28") (pin "1") (pinfunction "1_1") (pintype "passive"))
    )
    (net (code "54") (name "Net-(IC5-O3)") (class "Default")
      (node (ref "IC5") (pin "14") (pinfunction "O3_14") (pintype "open_collector"))
      (node (ref "K13") (pin "2") (pinfunction "2_2") (pintype "passive"))
      (node (ref "R29") (pin "1") (pinfunction "1_1") (pintype "passive"))
    )
    (net (code "55") (name "Net-(IC5-O4)") (class "Default")
      (node (ref "IC5") (pin "13") (pinfunction "O4_13") (pintype "open_collector"))
      (node (ref "K14") (pin "2") (pinfunction "2_2") (pintype "passive"))
      (node (ref "R30") (pin "1") (pinfunction "1_1") (pintype "passive"))
    )
    (net (code "56") (name "Net-(IC5-O5)") (class "Default")
      (node (ref "IC5") (pin "12") (pinfunction "O5_12") (pintype "open_collector"))
      (node (ref "K15") (pin "2") (pinfunction "2_2") (pintype "passive"))
      (node (ref "R31") (pin "1") (pinfunction "1_1") (pintype "passive"))
    )
    (net (code "57") (name "Net-(IC5-O6)") (class "Default")
      (node (ref "IC5") (pin "11") (pinfunction "O6_11") (pintype "open_collector"))
      (node (ref "K16") (pin "2") (pinfunction "2_2") (pintype "passive"))
      (node (ref "R32") (pin "1") (pinfunction "1_1") (pintype "passive"))
    )
    (net (code "58") (name "Net-(J1-Pad1)") (class "Default")
      (node (ref "J1") (pin "1") (pinfunction "1_1") (pintype "passive"))
      (node (ref "R1") (pin "2") (pinfunction "2_2") (pintype "passive"))
    )
    (net (code "59") (name "Net-(J2-Pad1)") (class "Default")
      (node (ref "J2") (pin "1") (pinfunction "1_1") (pintype "passive"))
      (node (ref "R3") (pin "2") (pinfunction "2_2") (pintype "passive"))
    )
    (net (code "60") (name "Net-(J3-Pad1)") (class "Default")
      (node (ref "J3") (pin "1") (pinfunction "1_1") (pintype "passive"))
      (node (ref "R5") (pin "2") (pinfunction "2_2") (pintype "passive"))
    )
    (net (code "61") (name "Net-(J4-Pad1)") (class "Default")
      (node (ref "J4") (pin "1") (pinfunction "1_1") (pintype "passive"))
      (node (ref "R7") (pin "2") (pinfunction "2_2") (pintype "passive"))
    )
    (net (code "62") (name "Net-(J5-Pad1)") (class "Default")
      (node (ref "J5") (pin "1") (pinfunction "1_1") (pintype "passive"))
      (node (ref "R9") (pin "2") (pinfunction "2_2") (pintype "passive"))
    )
    (net (code "63") (name "Net-(J6-Pad1)") (class "Default")
      (node (ref "J6") (pin "1") (pinfunction "1_1") (pintype "passive"))
      (node (ref "R11") (pin "2") (pinfunction "2_2") (pintype "passive"))
    )
    (net (code "64") (name "Net-(J7-Pad1)") (class "Default")
      (node (ref "J7") (pin "1") (pinfunction "1_1") (pintype "passive"))
      (node (ref "R13") (pin "2") (pinfunction "2_2") (pintype "passive"))
    )
    (net (code "65") (name "Net-(J8-Pad1)") (class "Default")
      (node (ref "J8") (pin "1") (pinfunction "1_1") (pintype "passive"))
      (node (ref "R15") (pin "2") (pinfunction "2_2") (pintype "passive"))
    )
    (net (code "66") (name "Net-(J9-Pad1)") (class "Default")
      (node (ref "J9") (pin "1") (pinfunction "1_1") (pintype "passive"))
      (node (ref "K16") (pin "P") (pinfunction "P_P") (pintype "passive"))
    )
    (net (code "67") (name "Net-(J9-Pad2)") (class "Default")
      (node (ref "J9") (pin "2") (pinfunction "2_2") (pintype "passive"))
      (node (ref "K16") (pin "S") (pinfunction "S_S") (pintype "passive"))
    )
    (net (code "68") (name "Net-(J10-Pad1)") (class "Default")
      (node (ref "J10") (pin "1") (pinfunction "1_1") (pintype "passive"))
      (node (ref "K15") (pin "P") (pinfunction "P_P") (pintype "passive"))
    )
    (net (code "69") (name "Net-(J10-Pad2)") (class "Default")
      (node (ref "J10") (pin "2") (pinfunction "2_2") (pintype "passive"))
      (node (ref "K15") (pin "S") (pinfunction "S_S") (pintype "passive"))
    )
    (net (code "70") (name "Net-(J11-Pad1)") (class "Default")
      (node (ref "J11") (pin "1") (pinfunction "1_1") (pintype "passive"))
      (node (ref "K14") (pin "P") (pinfunction "P_P") (pintype "passive"))
    )
    (net (code "71") (name "Net-(J11-Pad2)") (class "Default")
      (node (ref "J11") (pin "2") (pinfunction "2_2") (pintype "passive"))
      (node (ref "K14") (pin "S") (pinfunction "S_S") (pintype "passive"))
    )
    (net (code "72") (name "Net-(J12-Pad1)") (class "Default")
      (node (ref "J12") (pin "1") (pinfunction "1_1") (pintype "passive"))
      (node (ref "K13") (pin "P") (pinfunction "P_P") (pintype "passive"))
    )
    (net (code "73") (name "Net-(J12-Pad2)") (class "Default")
      (node (ref "J12") (pin "2") (pinfunction "2_2") (pintype "passive"))
      (node (ref "K13") (pin "S") (pinfunction "S_S") (pintype "passive"))
    )
    (net (code "74") (name "Net-(J13-Pad1)") (class "Default")
      (node (ref "J13") (pin "1") (pinfunction "1_1") (pintype "passive"))
      (node (ref "K12") (pin "P") (pinfunction "P_P") (pintype "passive"))
    )
    (net (code "75") (name "Net-(J13-Pad2)") (class "Default")
      (node (ref "J13") (pin "2") (pinfunction "2_2") (pintype "passive"))
      (node (ref "K12") (pin "S") (pinfunction "S_S") (pintype "passive"))
    )
    (net (code "76") (name "Net-(J14-Pad1)") (class "Default")
      (node (ref "J14") (pin "1") (pinfunction "1_1") (pintype "passive"))
      (node (ref "K11") (pin "P") (pinfunction "P_P") (pintype "passive"))
    )
    (net (code "77") (name "Net-(J14-Pad2)") (class "Default")
      (node (ref "J14") (pin "2") (pinfunction "2_2") (pintype "passive"))
      (node (ref "K11") (pin "S") (pinfunction "S_S") (pintype "passive"))
    )
    (net (code "78") (name "Net-(J15-Pad1)") (class "Default")
      (node (ref "J15") (pin "1") (pinfunction "1_1") (pintype "passive"))
      (node (ref "K10") (pin "P") (pinfunction "P_P") (pintype "passive"))
    )
    (net (code "79") (name "Net-(J15-Pad2)") (class "Default")
      (node (ref "J15") (pin "2") (pinfunction "2_2") (pintype "passive"))
      (node (ref "K10") (pin "S") (pinfunction "S_S") (pintype "passive"))
    )
    (net (code "80") (name "Net-(J16-Pad1)") (class "Default")
      (node (ref "J16") (pin "1") (pinfunction "1_1") (pintype "passive"))
      (node (ref "K9") (pin "P") (pinfunction "P_P") (pintype "passive"))
    )
    (net (code "81") (name "Net-(J16-Pad2)") (class "Default")
      (node (ref "J16") (pin "2") (pinfunction "2_2") (pintype "passive"))
      (node (ref "K9") (pin "S") (pinfunction "S_S") (pintype "passive"))
    )
    (net (code "82") (name "Net-(J17-Pad1)") (class "Default")
      (node (ref "J17") (pin "1") (pinfunction "1_1") (pintype "passive"))
      (node (ref "K8") (pin "P") (pinfunction "P_P") (pintype "passive"))
    )
    (net (code "83") (name "Net-(J17-Pad2)") (class "Default")
      (node (ref "J17") (pin "2") (pinfunction "2_2") (pintype "passive"))
      (node (ref "K8") (pin "S") (pinfunction "S_S") (pintype "passive"))
    )
    (net (code "84") (name "Net-(J18-Pad1)") (class "Default")
      (node (ref "J18") (pin "1") (pinfunction "1_1") (pintype "passive"))
      (node (ref "K7") (pin "P") (pinfunction "P_P") (pintype "passive"))
    )
    (net (code "85") (name "Net-(J18-Pad2)") (class "Default")
      (node (ref "J18") (pin "2") (pinfunction "2_2") (pintype "passive"))
      (node (ref "K7") (pin "S") (pinfunction "S_S") (pintype "passive"))
    )
    (net (code "86") (name "Net-(J19-Pad1)") (class "Default")
      (node (ref "J19") (pin "1") (pinfunction "1_1") (pintype "passive"))
      (node (ref "K6") (pin "P") (pinfunction "P_P") (pintype "passive"))
    )
    (net (code "87") (name "Net-(J19-Pad2)") (class "Default")
      (node (ref "J19") (pin "2") (pinfunction "2_2") (pintype "passive"))
      (node (ref "K6") (pin "S") (pinfunction "S_S") (pintype "passive"))
    )
    (net (code "88") (name "Net-(J20-Pad1)") (class "Default")
      (node (ref "J20") (pin "1") (pinfunction "1_1") (pintype "passive"))
      (node (ref "K5") (pin "P") (pinfunction "P_P") (pintype "passive"))
    )
    (net (code "89") (name "Net-(J20-Pad2)") (class "Default")
      (node (ref "J20") (pin "2") (pinfunction "2_2") (pintype "passive"))
      (node (ref "K5") (pin "S") (pinfunction "S_S") (pintype "passive"))
    )
    (net (code "90") (name "Net-(J21-Pad1)") (class "Default")
      (node (ref "J21") (pin "1") (pinfunction "1_1") (pintype "passive"))
      (node (ref "K4") (pin "P") (pinfunction "P_P") (pintype "passive"))
    )
    (net (code "91") (name "Net-(J21-Pad2)") (class "Default")
      (node (ref "J21") (pin "2") (pinfunction "2_2") (pintype "passive"))
      (node (ref "K4") (pin "S") (pinfunction "S_S") (pintype "passive"))
    )
    (net (code "92") (name "Net-(J22-Pad1)") (class "Default")
      (node (ref "J22") (pin "1") (pinfunction "1_1") (pintype "passive"))
      (node (ref "K3") (pin "P") (pinfunction "P_P") (pintype "passive"))
    )
    (net (code "93") (name "Net-(J22-Pad2)") (class "Default")
      (node (ref "J22") (pin "2") (pinfunction "2_2") (pintype "passive"))
      (node (ref "K3") (pin "S") (pinfunction "S_S") (pintype "passive"))
    )
    (net (code "94") (name "Net-(J23-Pad1)") (class "Default")
      (node (ref "J23") (pin "1") (pinfunction "1_1") (pintype "passive"))
      (node (ref "K2") (pin "P") (pinfunction "P_P") (pintype "passive"))
    )
    (net (code "95") (name "Net-(J23-Pad2)") (class "Default")
      (node (ref "J23") (pin "2") (pinfunction "2_2") (pintype "passive"))
      (node (ref "K2") (pin "S") (pinfunction "S_S") (pintype "passive"))
    )
    (net (code "96") (name "Net-(J24-Pad1)") (class "Default")
      (node (ref "J24") (pin "1") (pinfunction "1_1") (pintype "passive"))
      (node (ref "K1") (pin "P") (pinfunction "P_P") (pintype "passive"))
    )
    (net (code "97") (name "Net-(J24-Pad2)") (class "Default")
      (node (ref "J24") (pin "2") (pinfunction "2_2") (pintype "passive"))
      (node (ref "K1") (pin "S") (pinfunction "S_S") (pintype "passive"))
    )
    (net (code "98") (name "Net-(LED1-C)") (class "Default")
      (node (ref "LED1") (pin "K") (pinfunction "C_K") (pintype "passive"))
      (node (ref "R17") (pin "2") (pinfunction "2_2") (pintype "passive"))
    )
    (net (code "99") (name "Net-(LED2-C)") (class "Default")
      (node (ref "LED2") (pin "K") (pinfunction "C_K") (pintype "passive"))
      (node (ref "R18") (pin "2") (pinfunction "2_2") (pintype "passive"))
    )
    (net (code "100") (name "Net-(LED3-C)") (class "Default")
      (node (ref "LED3") (pin "K") (pinfunction "C_K") (pintype "passive"))
      (node (ref "R19") (pin "2") (pinfunction "2_2") (pintype "passive"))
    )
    (net (code "101") (name "Net-(LED4-C)") (class "Default")
      (node (ref "LED4") (pin "K") (pinfunction "C_K") (pintype "passive"))
      (node (ref "R20") (pin "2") (pinfunction "2_2") (pintype "passive"))
    )
    (net (code "102") (name "Net-(LED5-C)") (class "Default")
      (node (ref "LED5") (pin "K") (pinfunction "C_K") (pintype "passive"))
      (node (ref "R21") (pin "2") (pinfunction "2_2") (pintype "passive"))
    )
    (net (code "103") (name "Net-(LED6-C)") (class "Default")
      (node (ref "LED6") (pin "K") (pinfunction "C_K") (pintype "passive"))
      (node (ref "R22") (pin "2") (pinfunction "2_2") (pintype "passive"))
    )
    (net (code "104") (name "Net-(LED7-C)") (class "Default")
      (node (ref "LED7") (pin "K") (pinfunction "C_K") (pintype "passive"))
      (node (ref "R23") (pin "2") (pinfunction "2_2") (pintype "passive"))
    )
    (net (code "105") (name "Net-(LED8-C)") (class "Default")
      (node (ref "LED8") (pin "K") (pinfunction "C_K") (pintype "passive"))
      (node (ref "R24") (pin "2") (pinfunction "2_2") (pintype "passive"))
    )
    (net (code "106") (name "Net-(LED9-C)") (class "Default")
      (node (ref "LED9") (pin "K") (pinfunction "C_K") (pintype "passive"))
      (node (ref "R25") (pin "2") (pinfunction "2_2") (pintype "passive"))
    )
    (net (code "107") (name "Net-(LED10-C)") (class "Default")
      (node (ref "LED10") (pin "K") (pinfunction "C_K") (pintype "passive"))
      (node (ref "R26") (pin "2") (pinfunction "2_2") (pintype "passive"))
    )
    (net (code "108") (name "Net-(LED11-C)") (class "Default")
      (node (ref "LED11") (pin "K") (pinfunction "C_K") (pintype "passive"))
      (node (ref "R27") (pin "2") (pinfunction "2_2") (pintype "passive"))
    )
    (net (code "109") (name "Net-(LED12-C)") (class "Default")
      (node (ref "LED12") (pin "K") (pinfunction "C_K") (pintype "passive"))
      (node (ref "R28") (pin "2") (pinfunction "2_2") (pintype "passive"))
    )
    (net (code "110") (name "Net-(LED13-C)") (class "Default")
      (node (ref "LED13") (pin "K") (pinfunction "C_K") (pintype "passive"))
      (node (ref "R29") (pin "2") (pinfunction "2_2") (pintype "passive"))
    )
    (net (code "111") (name "Net-(LED14-C)") (class "Default")
      (node (ref "LED14") (pin "K") (pinfunction "C_K") (pintype "passive"))
      (node (ref "R30") (pin "2") (pinfunction "2_2") (pintype "passive"))
    )
    (net (code "112") (name "Net-(LED15-C)") (class "Default")
      (node (ref "LED15") (pin "K") (pinfunction "C_K") (pintype "passive"))
      (node (ref "R31") (pin "2") (pinfunction "2_2") (pintype "passive"))
    )
    (net (code "113") (name "Net-(LED16-C)") (class "Default")
      (node (ref "LED16") (pin "K") (pinfunction "C_K") (pintype "passive"))
      (node (ref "R32") (pin "2") (pinfunction "2_2") (pintype "passive"))
    )
    (net (code "114") (name "unconnected-(IC1-(OC1A)PD5-Pad19)") (class "Default")
      (node (ref "IC1") (pin "19") (pinfunction "(OC1A)PD5_19") (pintype "bidirectional"))
    )
    (net (code "115") (name "unconnected-(IC1-(OC1B)PD4-Pad18)") (class "Default")
      (node (ref "IC1") (pin "18") (pinfunction "(OC1B)PD4_18") (pintype "bidirectional"))
    )
    (net (code "116") (name "unconnected-(IC4-I3-Pad3)") (class "Default")
      (node (ref "IC4") (pin "3") (pinfunction "I3_3") (pintype "input"))
    )
    (net (code "117") (name "unconnected-(IC4-I4-Pad4)") (class "Default")
      (node (ref "IC4") (pin "4") (pinfunction "I4_4") (pintype "input"))
    )
    (net (code "118") (name "unconnected-(IC4-I5-Pad5)") (class "Default")
      (node (ref "IC4") (pin "5") (pinfunction "I5_5") (pintype "input"))
    )
    (net (code "119") (name "unconnected-(IC4-I6-Pad6)") (class "Default")
      (node (ref "IC4") (pin "6") (pinfunction "I6_6") (pintype "input"))
    )
    (net (code "120") (name "unconnected-(IC4-O3-Pad14)") (class "Default")
      (node (ref "IC4") (pin "14") (pinfunction "O3_14") (pintype "open_collector"))
    )
    (net (code "121") (name "unconnected-(IC4-O4-Pad13)") (class "Default")
      (node (ref "IC4") (pin "13") (pinfunction "O4_13") (pintype "open_collector"))
    )
    (net (code "122") (name "unconnected-(IC4-O5-Pad12)") (class "Default")
      (node (ref "IC4") (pin "12") (pinfunction "O5_12") (pintype "open_collector"))
    )
    (net (code "123") (name "unconnected-(IC4-O6-Pad11)") (class "Default")
      (node (ref "IC4") (pin "11") (pinfunction "O6_11") (pintype "open_collector"))
    )
    (net (code "124") (name "unconnected-(IC5-I7-Pad7)") (class "Default")
      (node (ref "IC5") (pin "7") (pinfunction "I7_7") (pintype "input"))
    )
    (net (code "125") (name "unconnected-(IC5-O7-Pad10)") (class "Default")
      (node (ref "IC5") (pin "10") (pinfunction "O7_10") (pintype "open_collector"))
    )
    (net (code "126") (name "unconnected-(K1-PadO)") (class "Default")
      (node (ref "K1") (pin "O") (pinfunction "O_O") (pintype "passive"))
    )
    (net (code "127") (name "unconnected-(K2-PadO)") (class "Default")
      (node (ref "K2") (pin "O") (pinfunction "O_O") (pintype "passive"))
    )
    (net (code "128") (name "unconnected-(K3-PadO)") (class "Default")
      (node (ref "K3") (pin "O") (pinfunction "O_O") (pintype "passive"))
    )
    (net (code "129") (name "unconnected-(K4-PadO)") (class "Default")
      (node (ref "K4") (pin "O") (pinfunction "O_O") (pintype "passive"))
    )
    (net (code "130") (name "unconnected-(K5-PadO)") (class "Default")
      (node (ref "K5") (pin "O") (pinfunction "O_O") (pintype "passive"))
    )
    (net (code "131") (name "unconnected-(K6-PadO)") (class "Default")
      (node (ref "K6") (pin "O") (pinfunction "O_O") (pintype "passive"))
    )
    (net (code "132") (name "unconnected-(K7-PadO)") (class "Default")
      (node (ref "K7") (pin "O") (pinfunction "O_O") (pintype "passive"))
    )
    (net (code "133") (name "unconnected-(K8-PadO)") (class "Default")
      (node (ref "K8") (pin "O") (pinfunction "O_O") (pintype "passive"))
    )
    (net (code "134") (name "unconnected-(K9-PadO)") (class "Default")
      (node (ref "K9") (pin "O") (pinfunction "O_O") (pintype "passive"))
    )
    (net (code "135") (name "unconnected-(K10-PadO)") (class "Default")
      (node (ref "K10") (pin "O") (pinfunction "O_O") (pintype "passive"))
    )
    (net (code "136") (name "unconnected-(K11-PadO)") (class "Default")
      (node (ref "K11") (pin "O") (pinfunction "O_O") (pintype "passive"))
    )
    (net (code "137") (name "unconnected-(K12-PadO)") (class "Default")
      (node (ref "K12") (pin "O") (pinfunction "O_O") (pintype "passive"))
    )
    (net (code "138") (name "unconnected-(K13-PadO)") (class "Default")
      (node (ref "K13") (pin "O") (pinfunction "O_O") (pintype "passive"))
    )
    (net (code "139") (name "unconnected-(K14-PadO)") (class "Default")
      (node (ref "K14") (pin "O") (pinfunction "O_O") (pintype "passive"))
    )
    (net (code "140") (name "unconnected-(K15-PadO)") (class "Default")
      (node (ref "K15") (pin "O") (pinfunction "O_O") (pintype "passive"))
    )
    (net (code "141") (name "unconnected-(K16-PadO)") (class "Default")
      (node (ref "K16") (pin "O") (pinfunction "O_O") (pintype "passive"))
    )
    (net (code "142") (name "unconnected-(SL1-Pad1)") (class "Default")
      (node (ref "SL1") (pin "1") (pinfunction "1_1") (pintype "passive"))
    )
    (net (code "143") (name "unconnected-(SL1-Pad3)") (class "Default")
      (node (ref "SL1") (pin "3") (pinfunction "3_3") (pintype "passive"))
    )
    (net (code "144") (name "unconnected-(SL1-Pad4)") (class "Default")
      (node (ref "SL1") (pin "4") (pinfunction "4_4") (pintype "passive"))
    )
    (net (code "145") (name "unconnected-(SL1-Pad5)") (class "Default")
      (node (ref "SL1") (pin "5") (pinfunction "5_5") (pintype "passive"))
    )
  )
)
